# H1FR20.net
KiCad netlist of a schematic drawn in EAGLE
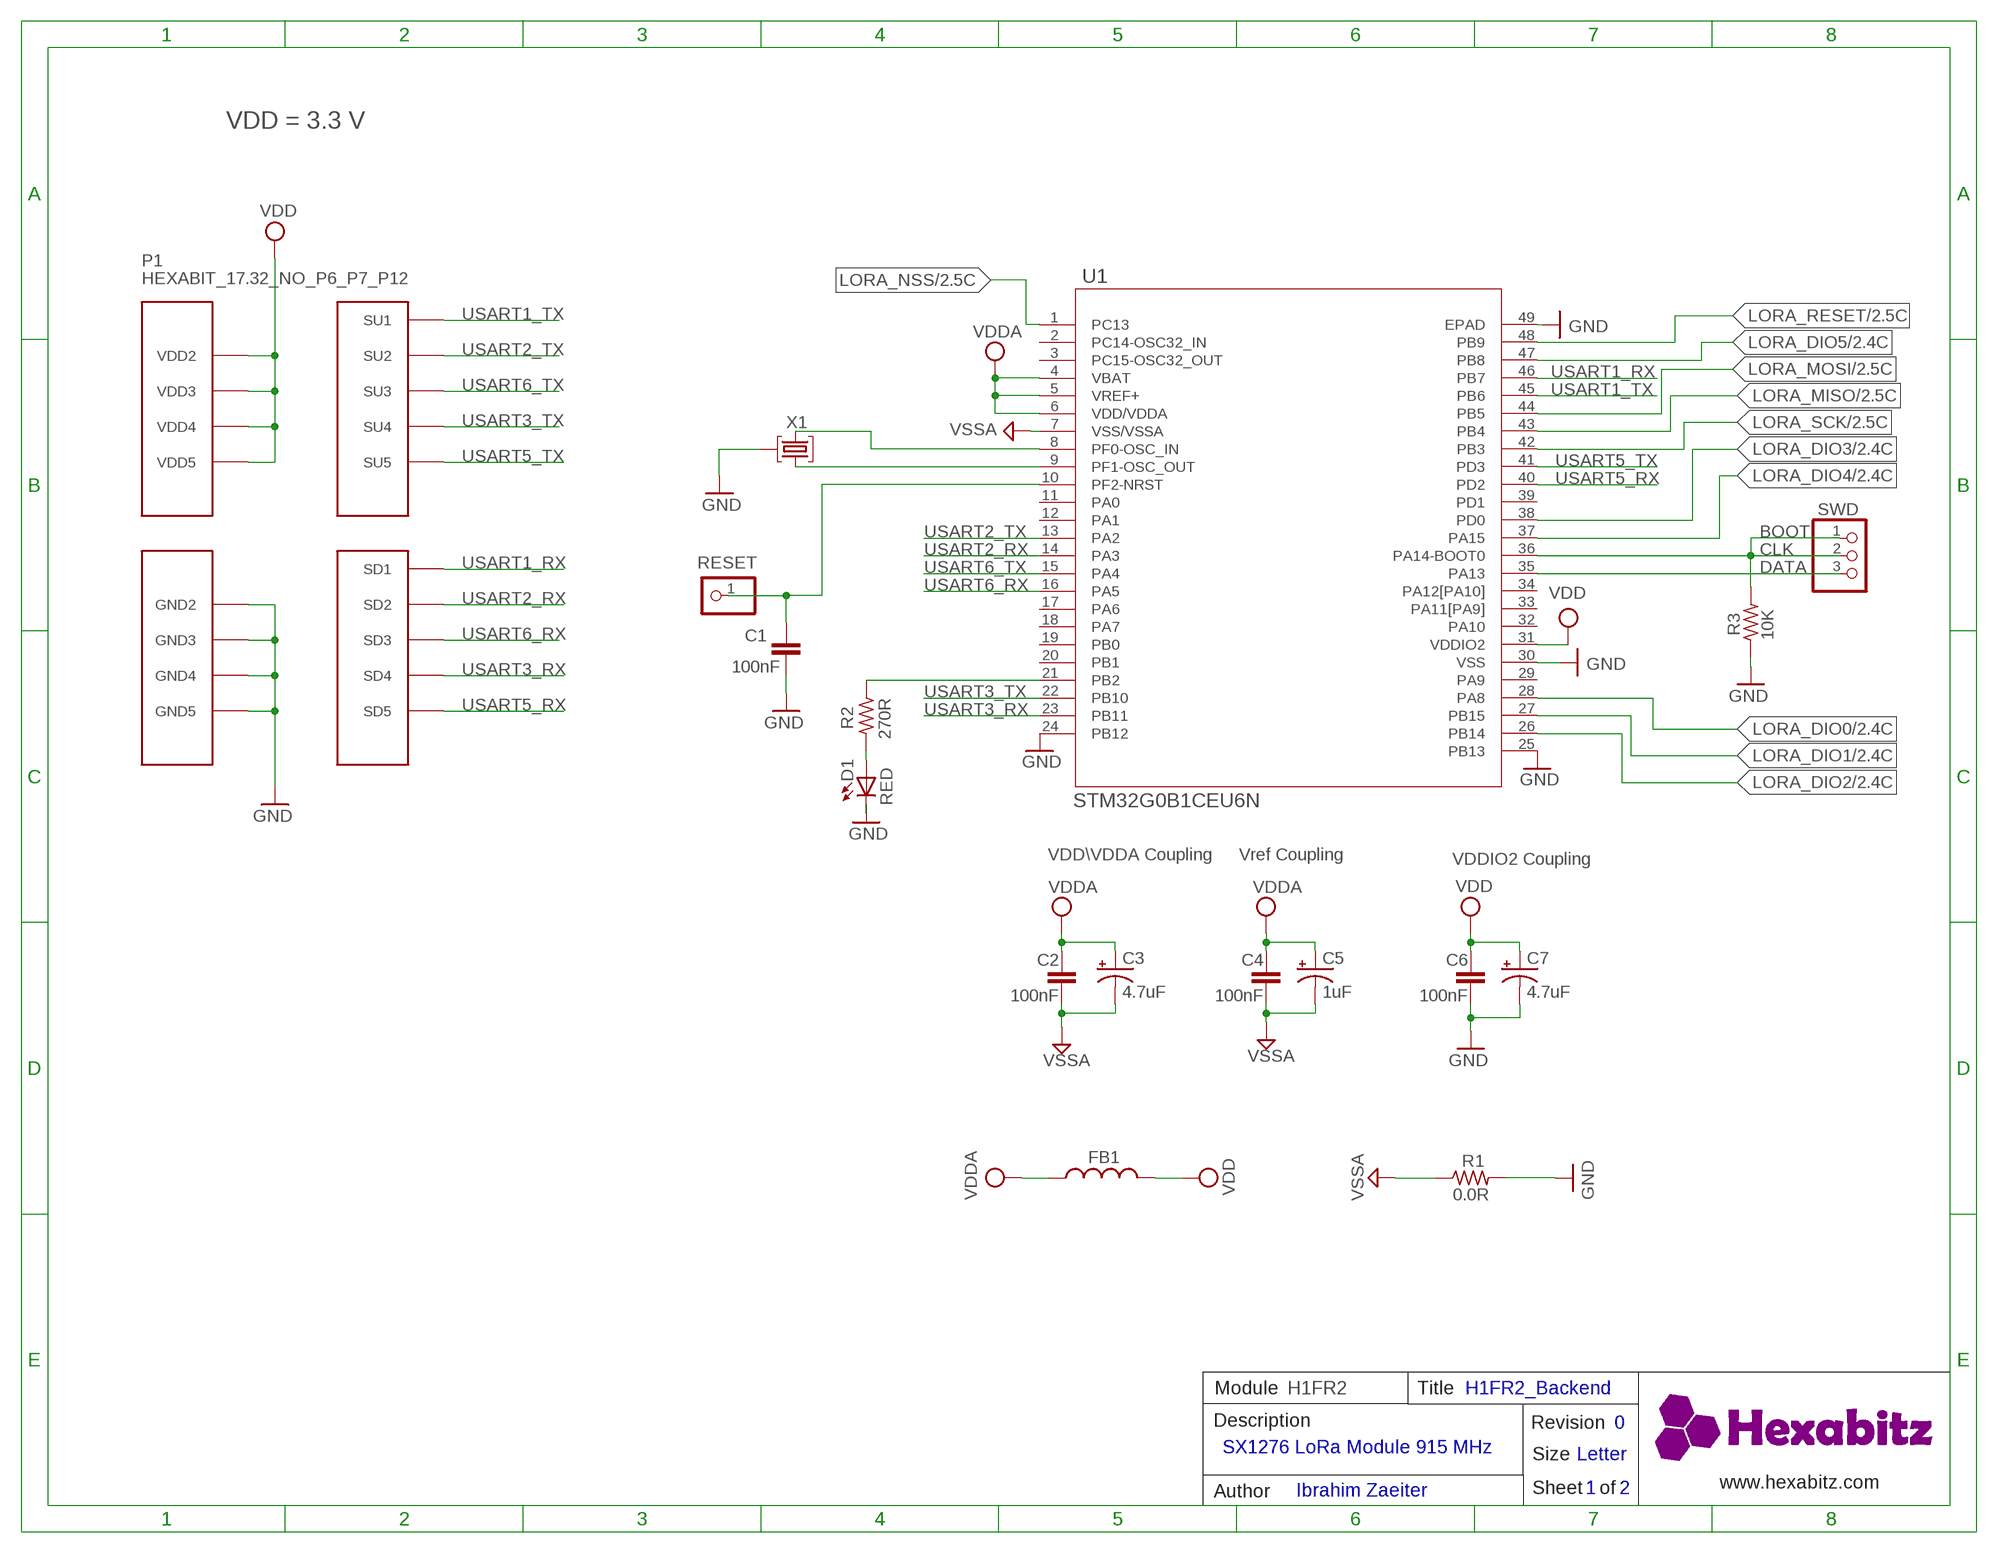
[diagram p0: schematic, sheet 1]
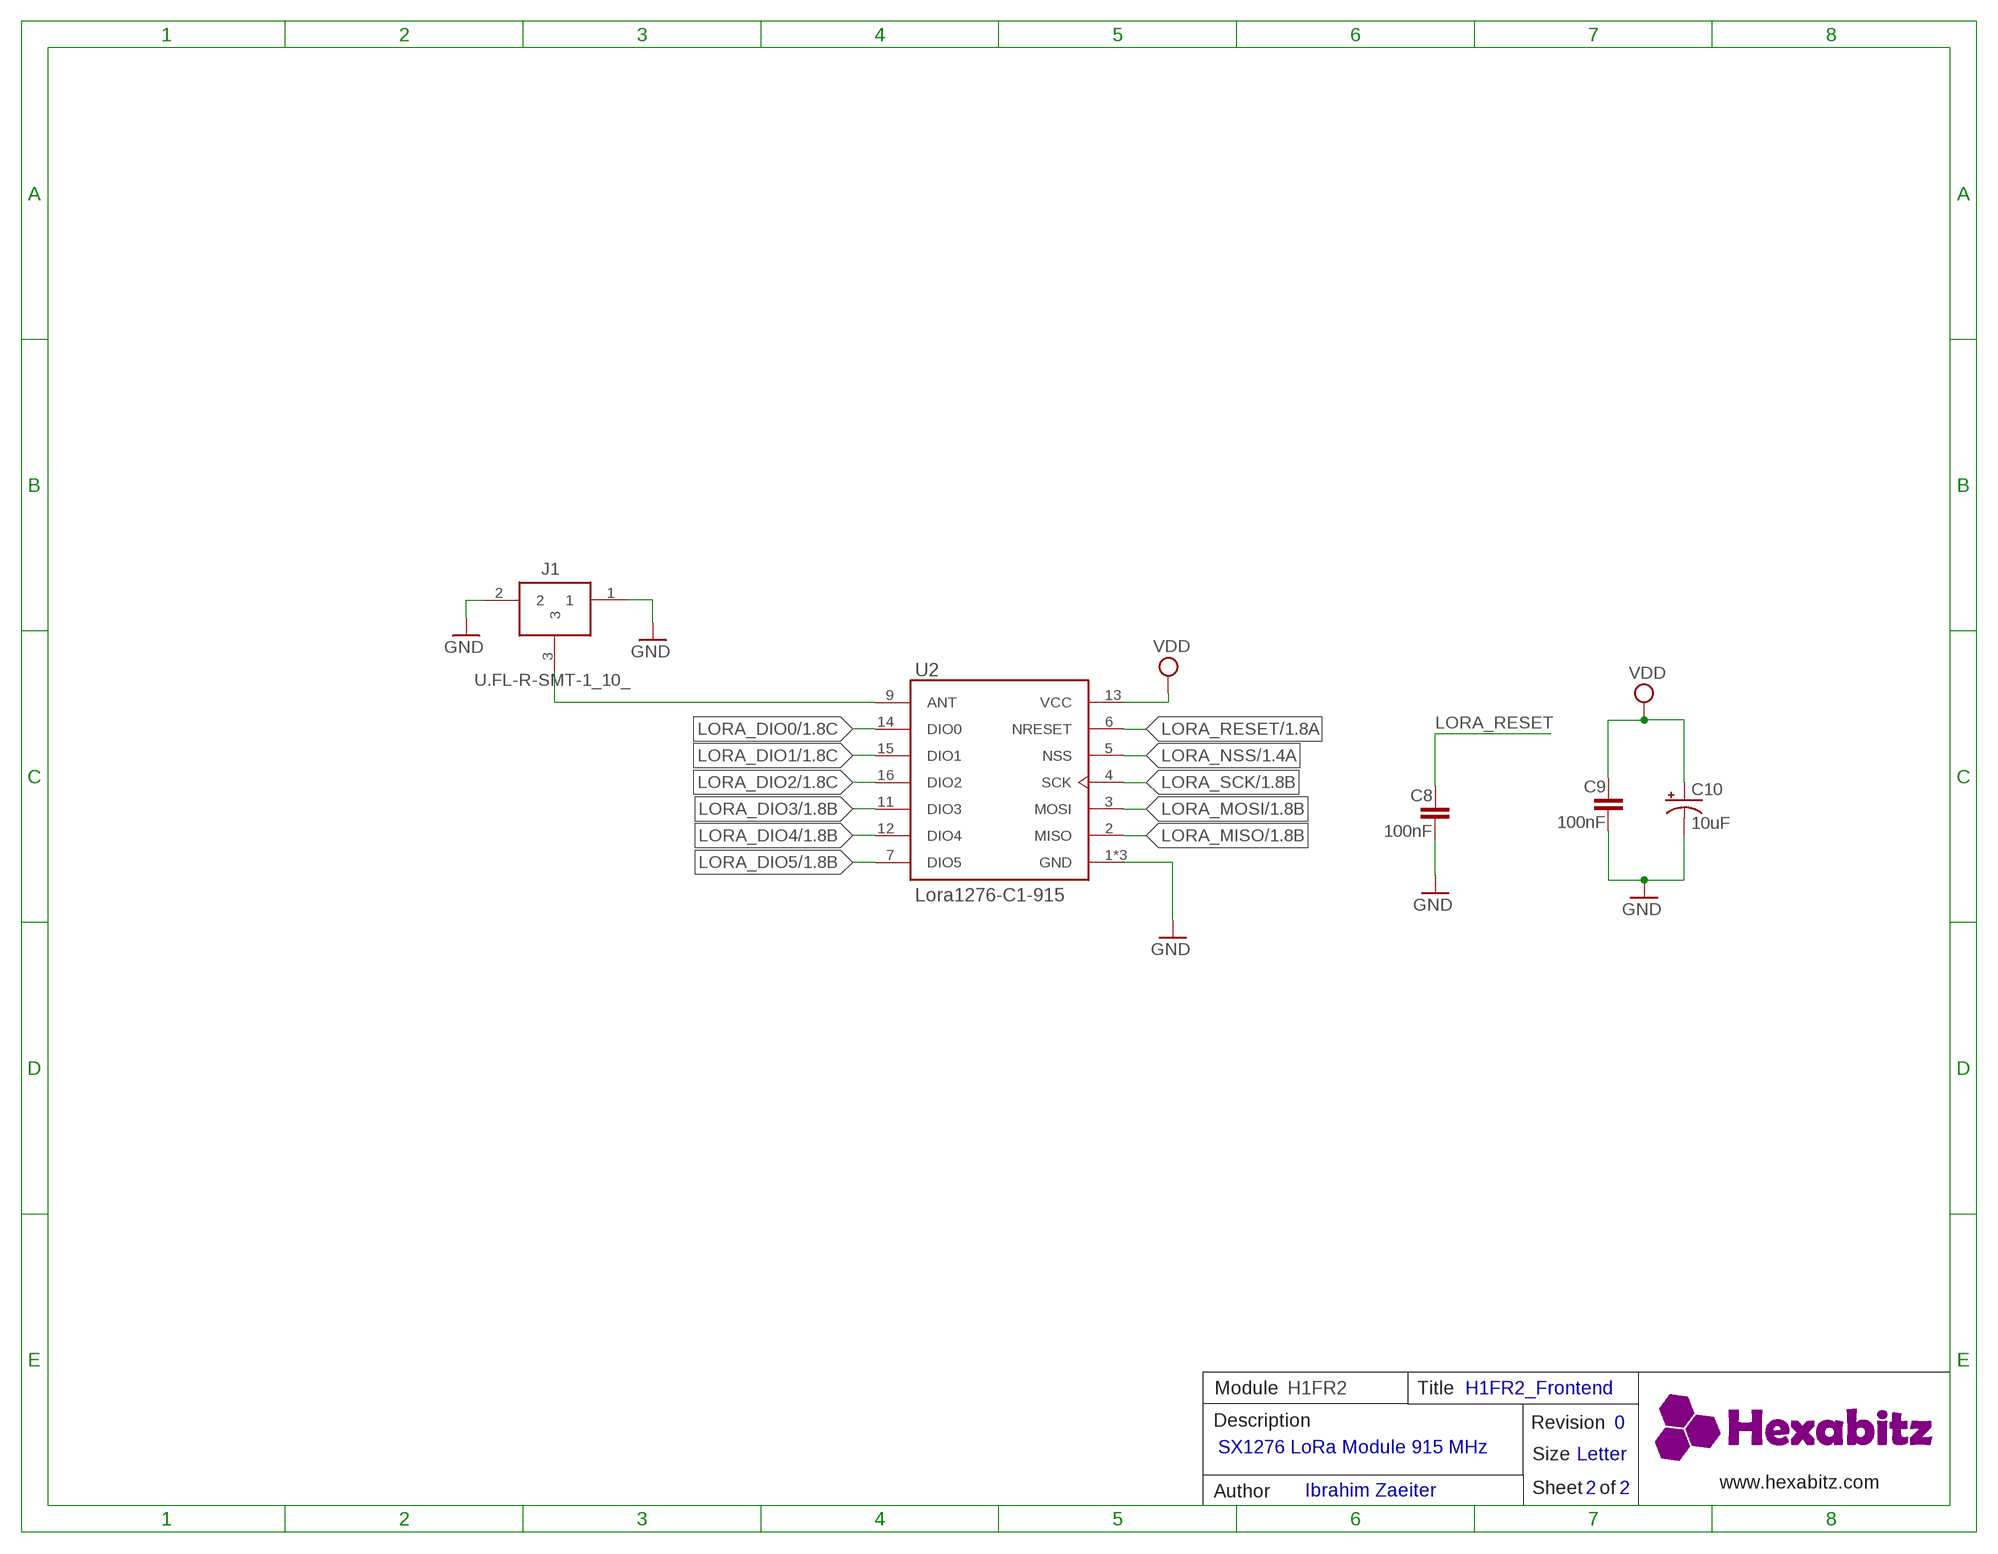
[diagram p1: schematic, sheet 2]

(export (version "E")
  (design (tool "Eeschema 10.0.6"))
  (components
    (comp (ref "C8")
      (value "100nF")
      (footprint "eagle-import:C-0603")
      (libsource (lib "eagle-import") (part "C-0603"))
    )
    (comp (ref "C9")
      (value "100nF")
      (footprint "eagle-import:C-0603")
      (libsource (lib "eagle-import") (part "C-0603"))
    )
    (comp (ref "C10")
      (value "10uF")
      (footprint "eagle-import:C-1210-POL")
      (libsource (lib "eagle-import") (part "C-1210-POL"))
    )
    (comp (ref "J1")
      (value "U.FL-R-SMT-1_10_")
      (footprint "eagle-import:U.FL-R-SMT-1(10)")
      (fields
        (field (name "MANUFACTURER_PART_NUMBER") "U.FL-R-SMT-1(10)")
        (field (name "MOUSER_PART_NUMBER") "798-U.FL-R-SMT-110")
      )
      (libsource (lib "eagle-import") (part "U.FL-R-SMT-1_10_"))
    )
    (comp (ref "U2")
      (value "Lora1276-C1-915")
      (footprint "eagle-import:LORA127X-C1")
      (fields (field (name "MF") "AI-Thinker") (field (name "MP") "ESP8266-12E/ESP-12E"))
      (libsource (lib "eagle-import") (part "LORA127X-C1"))
    )
    (comp (ref "C1")
      (value "100nF")
      (footprint "eagle-import:C-0603")
      (libsource (lib "eagle-import") (part "C-0603"))
    )
    (comp (ref "C2")
      (value "100nF")
      (footprint "eagle-import:C-0603")
      (libsource (lib "eagle-import") (part "C-0603"))
    )
    (comp (ref "C3")
      (value "4.7uF")
      (footprint "eagle-import:C-0805-POL")
      (libsource (lib "eagle-import") (part "C-0805-POL"))
    )
    (comp (ref "C4")
      (value "100nF")
      (footprint "eagle-import:C-0603")
      (libsource (lib "eagle-import") (part "C-0603"))
    )
    (comp (ref "C5")
      (value "1uF")
      (footprint "eagle-import:C-0805-POL")
      (libsource (lib "eagle-import") (part "C-0805-POL"))
    )
    (comp (ref "C6")
      (value "100nF")
      (footprint "eagle-import:C-0603")
      (libsource (lib "eagle-import") (part "C-0603"))
    )
    (comp (ref "C7")
      (value "4.7uF")
      (footprint "eagle-import:C-0805-POL")
      (libsource (lib "eagle-import") (part "C-0805-POL"))
    )
    (comp (ref "D1")
      (value "RED")
      (footprint "eagle-import:VLMS1300-GS08")
      (fields
        (field (name "MPN") "VLMS1300-GS08")
        (field (name "MFN") "Vishay")
        (field (name "MPN_1") "VLMS1300-GS08")
        (field (name "OCTOPART_URL") "https://octopart.com/vlms1300-gs08-vishay-21709201?r=sp&s=_gcP4_q8T1SC6PJQPTQ9yA")
      )
      (libsource (lib "eagle-import") (part "VLMS1300-GS08"))
    )
    (comp (ref "FB1")
      (value "FB-0603")
      (footprint "eagle-import:FB-0603")
      (libsource (lib "eagle-import") (part "FB-0603"))
    )
    (comp (ref "P1")
      (value "HEXABIT_17.32_NO_P6_P7_P12")
      (footprint "eagle-import:HEXABIT_17.32_NO_P6_P7_P12")
      (libsource (lib "eagle-import") (part "HEXABIT_?_NO_P6_P7_P1217.32"))
    )
    (comp (ref "R1")
      (value "0.0R")
      (footprint "eagle-import:R-0603")
      (libsource (lib "eagle-import") (part "R-0603"))
    )
    (comp (ref "R2")
      (value "270R")
      (footprint "eagle-import:R-0603")
      (libsource (lib "eagle-import") (part "R-0603"))
    )
    (comp (ref "R3")
      (value "10K")
      (footprint "eagle-import:R-0603")
      (libsource (lib "eagle-import") (part "R-0603"))
    )
    (comp (ref "RESET")
      (value "R")
      (footprint "eagle-import:1X01")
      (fields (field (name "MPN") "87227-1"))
      (libsource (lib "eagle-import") (part "PINHD-1X1"))
    )
    (comp (ref "SWD")
      (value "PINHD-1X3SWD")
      (footprint "eagle-import:SWD")
      (libsource (lib "eagle-import") (part "PINHD-1X3SWD"))
    )
    (comp (ref "U1")
      (value "STM32G0B1CEU6N")
      (footprint "eagle-import:HEXABITZ_ICS_QFN_B1CEU6_STM-L")
      (libsource (lib "eagle-import") (part "STM32G0B1CEU6N"))
    )
    (comp (ref "X1")
      (value "XTALL_CSTCE8M00G52")
      (footprint "eagle-import:XTALL_CSTCE8M00G52")
      (fields (field (name "MPN") "CSTCE8M00G52Z-R0"))
      (libsource (lib "eagle-import") (part "XTALL_CSTCE8M00G52"))
    )
  )
  (nets
    (net (code "1") (name "CLK") (class "Default")
      (node (ref "R3") (pin "2") (pinfunction "2_2") (pintype "passive"))
      (node (ref "SWD") (pin "1") (pinfunction "1_1") (pintype "passive"))
      (node (ref "SWD") (pin "2") (pinfunction "2_2") (pintype "passive"))
      (node (ref "U1") (pin "36") (pinfunction "PA14-BOOT0_36") (pintype "bidirectional"))
    )
    (net (code "2") (name "DATA") (class "Default")
      (node (ref "SWD") (pin "3") (pinfunction "3_3") (pintype "passive"))
      (node (ref "U1") (pin "35") (pinfunction "PA13_35") (pintype "bidirectional"))
    )
    (net (code "3") (name "GND") (class "Default")
      (node (ref "C1") (pin "2") (pinfunction "2_2") (pintype "passive"))
      (node (ref "C10") (pin "2") (pinfunction "-_2") (pintype "passive"))
      (node (ref "C6") (pin "2") (pinfunction "2_2") (pintype "passive"))
      (node (ref "C7") (pin "2") (pinfunction "-_2") (pintype "passive"))
      (node (ref "C8") (pin "2") (pinfunction "2_2") (pintype "passive"))
      (node (ref "C9") (pin "2") (pinfunction "2_2") (pintype "passive"))
      (node (ref "D1") (pin "C") (pinfunction "C_C") (pintype "passive"))
      (node (ref "J1") (pin "1") (pinfunction "1_1") (pintype "bidirectional"))
      (node (ref "J1") (pin "2") (pinfunction "2_2") (pintype "bidirectional"))
      (node (ref "P1") (pin "PAD_PD10") (pinfunction "GND4_PAD_PD10") (pintype "power_in"))
      (node (ref "P1") (pin "PAD_PD11") (pinfunction "GND5_PAD_PD11") (pintype "power_in"))
      (node (ref "P1") (pin "PAD_PD8") (pinfunction "GND2_PAD_PD8") (pintype "power_in"))
      (node (ref "P1") (pin "PAD_PD9") (pinfunction "GND3_PAD_PD9") (pintype "power_in"))
      (node (ref "R1") (pin "2") (pinfunction "2_2") (pintype "passive"))
      (node (ref "R3") (pin "1") (pinfunction "1_1") (pintype "passive"))
      (node (ref "U1") (pin "24") (pinfunction "PB12_24") (pintype "bidirectional"))
      (node (ref "U1") (pin "25") (pinfunction "PB13_25") (pintype "bidirectional"))
      (node (ref "U1") (pin "30") (pinfunction "VSS_30") (pintype "passive"))
      (node (ref "U1") (pin "49") (pinfunction "EPAD_49") (pintype "passive"))
      (node (ref "U2") (pin "1") (pinfunction "GND_1") (pintype "power_in"))
      (node (ref "U2") (pin "10") (pinfunction "GND_10") (pintype "power_in"))
      (node (ref "U2") (pin "8") (pinfunction "GND_8") (pintype "power_in"))
      (node (ref "X1") (pin "P$2") (pinfunction "2_P$2") (pintype "passive"))
    )
    (net (code "4") (name "LORA_DIO0") (class "Default")
      (node (ref "U1") (pin "28") (pinfunction "PA8_28") (pintype "bidirectional"))
      (node (ref "U2") (pin "14") (pinfunction "DIO0_14") (pintype "bidirectional"))
    )
    (net (code "5") (name "LORA_DIO1") (class "Default")
      (node (ref "U1") (pin "27") (pinfunction "PB15_27") (pintype "bidirectional"))
      (node (ref "U2") (pin "15") (pinfunction "DIO1_15") (pintype "bidirectional"))
    )
    (net (code "6") (name "LORA_DIO2") (class "Default")
      (node (ref "U1") (pin "26") (pinfunction "PB14_26") (pintype "bidirectional"))
      (node (ref "U2") (pin "16") (pinfunction "DIO2_16") (pintype "bidirectional"))
    )
    (net (code "7") (name "LORA_DIO3") (class "Default")
      (node (ref "U1") (pin "38") (pinfunction "PD0_38") (pintype "bidirectional"))
      (node (ref "U2") (pin "11") (pinfunction "DIO3_11") (pintype "bidirectional"))
    )
    (net (code "8") (name "LORA_DIO4") (class "Default")
      (node (ref "U1") (pin "37") (pinfunction "PA15_37") (pintype "bidirectional"))
      (node (ref "U2") (pin "12") (pinfunction "DIO4_12") (pintype "bidirectional"))
    )
    (net (code "9") (name "LORA_DIO5") (class "Default")
      (node (ref "U1") (pin "47") (pinfunction "PB8_47") (pintype "bidirectional"))
      (node (ref "U2") (pin "7") (pinfunction "DIO5_7") (pintype "bidirectional"))
    )
    (net (code "10") (name "LORA_MISO") (class "Default")
      (node (ref "U1") (pin "43") (pinfunction "PB4_43") (pintype "bidirectional"))
      (node (ref "U2") (pin "2") (pinfunction "MISO_2") (pintype "bidirectional"))
    )
    (net (code "11") (name "LORA_MOSI") (class "Default")
      (node (ref "U1") (pin "44") (pinfunction "PB5_44") (pintype "bidirectional"))
      (node (ref "U2") (pin "3") (pinfunction "MOSI_3") (pintype "bidirectional"))
    )
    (net (code "12") (name "LORA_NSS") (class "Default")
      (node (ref "U1") (pin "1") (pinfunction "PC13_1") (pintype "bidirectional"))
      (node (ref "U2") (pin "5") (pinfunction "NSS_5") (pintype "input"))
    )
    (net (code "13") (name "LORA_RESET") (class "Default")
      (node (ref "C8") (pin "1") (pinfunction "1_1") (pintype "passive"))
      (node (ref "U1") (pin "48") (pinfunction "PB9_48") (pintype "bidirectional"))
      (node (ref "U2") (pin "6") (pinfunction "NRESET_6") (pintype "input"))
    )
    (net (code "14") (name "LORA_SCK") (class "Default")
      (node (ref "U1") (pin "42") (pinfunction "PB3_42") (pintype "bidirectional"))
      (node (ref "U2") (pin "4") (pinfunction "SCK_4") (pintype "input"))
    )
    (net (code "15") (name "Net-(D1-PadA)") (class "Default")
      (node (ref "D1") (pin "A") (pinfunction "A_A") (pintype "passive"))
      (node (ref "R2") (pin "2") (pinfunction "2_2") (pintype "passive"))
    )
    (net (code "16") (name "Net-(U1-PB2)") (class "Default")
      (node (ref "R2") (pin "1") (pinfunction "1_1") (pintype "passive"))
      (node (ref "U1") (pin "21") (pinfunction "PB2_21") (pintype "bidirectional"))
    )
    (net (code "17") (name "Net-(U1-PF0-OSC_IN)") (class "Default")
      (node (ref "U1") (pin "8") (pinfunction "PF0-OSC_IN_8") (pintype "bidirectional"))
      (node (ref "X1") (pin "P$3") (pinfunction "3_P$3") (pintype "passive"))
    )
    (net (code "18") (name "Net-(U1-PF1-OSC_OUT)") (class "Default")
      (node (ref "U1") (pin "9") (pinfunction "PF1-OSC_OUT_9") (pintype "bidirectional"))
      (node (ref "X1") (pin "P$1") (pinfunction "1_P$1") (pintype "passive"))
    )
    (net (code "19") (name "Net-(U1-PF2-NRST)") (class "Default")
      (node (ref "C1") (pin "1") (pinfunction "1_1") (pintype "passive"))
      (node (ref "RESET") (pin "1") (pinfunction "1_1") (pintype "passive"))
      (node (ref "U1") (pin "10") (pinfunction "PF2-NRST_10") (pintype "bidirectional"))
    )
    (net (code "20") (name "Net-(U2-ANT)") (class "Default")
      (node (ref "J1") (pin "3") (pinfunction "3_3") (pintype "bidirectional"))
      (node (ref "U2") (pin "9") (pinfunction "ANT_9") (pintype "passive"))
    )
    (net (code "21") (name "USART1_RX") (class "Default")
      (node (ref "P1") (pin "PAD_PD1") (pinfunction "SD1_PAD_PD1") (pintype "bidirectional"))
      (node (ref "U1") (pin "46") (pinfunction "PB7_46") (pintype "bidirectional"))
    )
    (net (code "22") (name "USART1_TX") (class "Default")
      (node (ref "P1") (pin "PAD_PU1") (pinfunction "SU1_PAD_PU1") (pintype "bidirectional"))
      (node (ref "U1") (pin "45") (pinfunction "PB6_45") (pintype "bidirectional"))
    )
    (net (code "23") (name "USART2_RX") (class "Default")
      (node (ref "P1") (pin "PAD_PD2") (pinfunction "SD2_PAD_PD2") (pintype "bidirectional"))
      (node (ref "U1") (pin "14") (pinfunction "PA3_14") (pintype "bidirectional"))
    )
    (net (code "24") (name "USART2_TX") (class "Default")
      (node (ref "P1") (pin "PAD_PU2") (pinfunction "SU2_PAD_PU2") (pintype "bidirectional"))
      (node (ref "U1") (pin "13") (pinfunction "PA2_13") (pintype "bidirectional"))
    )
    (net (code "25") (name "USART3_RX") (class "Default")
      (node (ref "P1") (pin "PAD_PD4") (pinfunction "SD4_PAD_PD4") (pintype "bidirectional"))
      (node (ref "U1") (pin "23") (pinfunction "PB11_23") (pintype "bidirectional"))
    )
    (net (code "26") (name "USART3_TX") (class "Default")
      (node (ref "P1") (pin "PAD_PU4") (pinfunction "SU4_PAD_PU4") (pintype "bidirectional"))
      (node (ref "U1") (pin "22") (pinfunction "PB10_22") (pintype "bidirectional"))
    )
    (net (code "27") (name "USART5_RX") (class "Default")
      (node (ref "P1") (pin "PAD_PD5") (pinfunction "SD5_PAD_PD5") (pintype "bidirectional"))
      (node (ref "U1") (pin "40") (pinfunction "PD2_40") (pintype "bidirectional"))
    )
    (net (code "28") (name "USART5_TX") (class "Default")
      (node (ref "P1") (pin "PAD_PU5") (pinfunction "SU5_PAD_PU5") (pintype "bidirectional"))
      (node (ref "U1") (pin "41") (pinfunction "PD3_41") (pintype "bidirectional"))
    )
    (net (code "29") (name "USART6_RX") (class "Default")
      (node (ref "P1") (pin "PAD_PD3") (pinfunction "SD3_PAD_PD3") (pintype "bidirectional"))
      (node (ref "U1") (pin "16") (pinfunction "PA5_16") (pintype "bidirectional"))
    )
    (net (code "30") (name "USART6_TX") (class "Default")
      (node (ref "P1") (pin "PAD_PU3") (pinfunction "SU3_PAD_PU3") (pintype "bidirectional"))
      (node (ref "U1") (pin "15") (pinfunction "PA4_15") (pintype "bidirectional"))
    )
    (net (code "31") (name "VDD") (class "Default")
      (node (ref "C10") (pin "1") (pinfunction "+_1") (pintype "passive"))
      (node (ref "C6") (pin "1") (pinfunction "1_1") (pintype "passive"))
      (node (ref "C7") (pin "1") (pinfunction "+_1") (pintype "passive"))
      (node (ref "C9") (pin "1") (pinfunction "1_1") (pintype "passive"))
      (node (ref "FB1") (pin "2") (pinfunction "2_2") (pintype "passive"))
      (node (ref "P1") (pin "PAD_PU10") (pinfunction "VDD4_PAD_PU10") (pintype "power_in"))
      (node (ref "P1") (pin "PAD_PU11") (pinfunction "VDD5_PAD_PU11") (pintype "power_in"))
      (node (ref "P1") (pin "PAD_PU8") (pinfunction "VDD2_PAD_PU8") (pintype "power_in"))
      (node (ref "P1") (pin "PAD_PU9") (pinfunction "VDD3_PAD_PU9") (pintype "power_in"))
      (node (ref "U1") (pin "31") (pinfunction "VDDIO2_31") (pintype "power_in"))
      (node (ref "U2") (pin "13") (pinfunction "VCC_13") (pintype "power_in"))
    )
    (net (code "32") (name "VDDA") (class "Default")
      (node (ref "C2") (pin "1") (pinfunction "1_1") (pintype "passive"))
      (node (ref "C3") (pin "1") (pinfunction "+_1") (pintype "passive"))
      (node (ref "C4") (pin "1") (pinfunction "1_1") (pintype "passive"))
      (node (ref "C5") (pin "1") (pinfunction "+_1") (pintype "passive"))
      (node (ref "FB1") (pin "1") (pinfunction "1_1") (pintype "passive"))
      (node (ref "U1") (pin "4") (pinfunction "VBAT_4") (pintype "power_in"))
      (node (ref "U1") (pin "5") (pinfunction "VREF+_5") (pintype "power_in"))
      (node (ref "U1") (pin "6") (pinfunction "VDD/VDDA_6") (pintype "power_in"))
    )
    (net (code "33") (name "VSSA") (class "Default")
      (node (ref "C2") (pin "2") (pinfunction "2_2") (pintype "passive"))
      (node (ref "C3") (pin "2") (pinfunction "-_2") (pintype "passive"))
      (node (ref "C4") (pin "2") (pinfunction "2_2") (pintype "passive"))
      (node (ref "C5") (pin "2") (pinfunction "-_2") (pintype "passive"))
      (node (ref "R1") (pin "1") (pinfunction "1_1") (pintype "passive"))
      (node (ref "U1") (pin "7") (pinfunction "VSS/VSSA_7") (pintype "passive"))
    )
    (net (code "34") (name "unconnected-(U1-PA0-Pad11)") (class "Default")
      (node (ref "U1") (pin "11") (pinfunction "PA0_11") (pintype "bidirectional"))
    )
    (net (code "35") (name "unconnected-(U1-PA1-Pad12)") (class "Default")
      (node (ref "U1") (pin "12") (pinfunction "PA1_12") (pintype "bidirectional"))
    )
    (net (code "36") (name "unconnected-(U1-PA6-Pad17)") (class "Default")
      (node (ref "U1") (pin "17") (pinfunction "PA6_17") (pintype "bidirectional"))
    )
    (net (code "37") (name "unconnected-(U1-PA7-Pad18)") (class "Default")
      (node (ref "U1") (pin "18") (pinfunction "PA7_18") (pintype "bidirectional"))
    )
    (net (code "38") (name "unconnected-(U1-PA9-Pad29)") (class "Default")
      (node (ref "U1") (pin "29") (pinfunction "PA9_29") (pintype "bidirectional"))
    )
    (net (code "39") (name "unconnected-(U1-PA10-Pad32)") (class "Default")
      (node (ref "U1") (pin "32") (pinfunction "PA10_32") (pintype "bidirectional"))
    )
    (net (code "40") (name "unconnected-(U1-PA11[PA9]-Pad33)") (class "Default")
      (node (ref "U1") (pin "33") (pinfunction "PA11[PA9]_33") (pintype "bidirectional"))
    )
    (net (code "41") (name "unconnected-(U1-PA12[PA10]-Pad34)") (class "Default")
      (node (ref "U1") (pin "34") (pinfunction "PA12[PA10]_34") (pintype "bidirectional"))
    )
    (net (code "42") (name "unconnected-(U1-PB0-Pad19)") (class "Default")
      (node (ref "U1") (pin "19") (pinfunction "PB0_19") (pintype "bidirectional"))
    )
    (net (code "43") (name "unconnected-(U1-PB1-Pad20)") (class "Default")
      (node (ref "U1") (pin "20") (pinfunction "PB1_20") (pintype "bidirectional"))
    )
    (net (code "44") (name "unconnected-(U1-PC14-OSC32_IN-Pad2)") (class "Default")
      (node (ref "U1") (pin "2") (pinfunction "PC14-OSC32_IN_2") (pintype "bidirectional"))
    )
    (net (code "45") (name "unconnected-(U1-PC15-OSC32_OUT-Pad3)") (class "Default")
      (node (ref "U1") (pin "3") (pinfunction "PC15-OSC32_OUT_3") (pintype "bidirectional"))
    )
    (net (code "46") (name "unconnected-(U1-PD1-Pad39)") (class "Default")
      (node (ref "U1") (pin "39") (pinfunction "PD1_39") (pintype "bidirectional"))
    )
  )
)
